# HP32W_proto.net
KiCad netlist of a schematic drawn in EAGLE
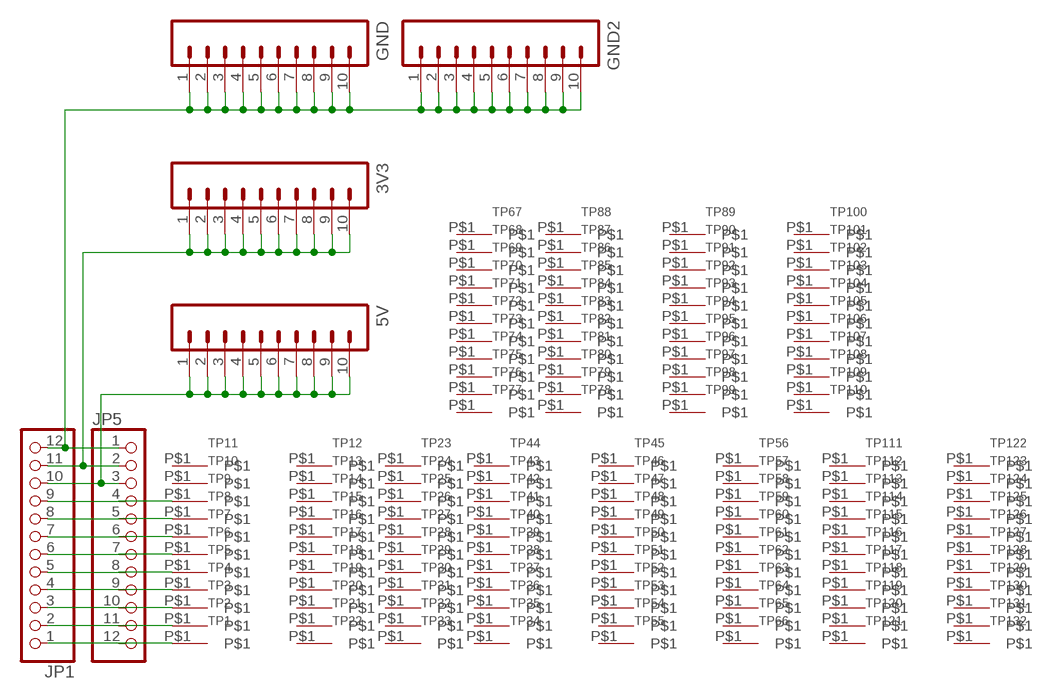
[diagram p0: schematic, sheet 1]

(export (version "E")
  (design (tool "Eeschema 10.0.6"))
  (components
    (comp (ref "3V3")
      (value "M10\"")
      (footprint "eagle-import:1X10")
      (libsource (lib "eagle-import") (part "M10{dblquote}"))
    )
    (comp (ref "5V")
      (value "M10\"")
      (footprint "eagle-import:1X10")
      (libsource (lib "eagle-import") (part "M10{dblquote}"))
    )
    (comp (ref "GND")
      (value "M10\"")
      (footprint "eagle-import:1X10")
      (libsource (lib "eagle-import") (part "M10{dblquote}"))
    )
    (comp (ref "GND2")
      (value "M10\"")
      (footprint "eagle-import:1X10")
      (libsource (lib "eagle-import") (part "M10{dblquote}"))
    )
    (comp (ref "JP1")
      (value "PINHD-1X12-CB")
      (footprint "eagle-import:1X12-CB")
      (libsource (lib "eagle-import") (part "PINHD-1X12-CB"))
    )
    (comp (ref "JP5")
      (value "PINHD-1X12-CB")
      (footprint "eagle-import:1X12-CB")
      (libsource (lib "eagle-import") (part "PINHD-1X12-CB"))
    )
    (comp (ref "TP1")
      (value "FLOWERPIN")
      (footprint "eagle-import:FLOWERPIN")
      (libsource (lib "eagle-import") (part "FLOWERPIN"))
    )
    (comp (ref "TP2")
      (value "FLOWERPIN")
      (footprint "eagle-import:FLOWERPIN")
      (libsource (lib "eagle-import") (part "FLOWERPIN"))
    )
    (comp (ref "TP3")
      (value "FLOWERPIN")
      (footprint "eagle-import:FLOWERPIN")
      (libsource (lib "eagle-import") (part "FLOWERPIN"))
    )
    (comp (ref "TP4")
      (value "FLOWERPIN")
      (footprint "eagle-import:FLOWERPIN")
      (libsource (lib "eagle-import") (part "FLOWERPIN"))
    )
    (comp (ref "TP5")
      (value "FLOWERPIN")
      (footprint "eagle-import:FLOWERPIN")
      (libsource (lib "eagle-import") (part "FLOWERPIN"))
    )
    (comp (ref "TP6")
      (value "FLOWERPIN")
      (footprint "eagle-import:FLOWERPIN")
      (libsource (lib "eagle-import") (part "FLOWERPIN"))
    )
    (comp (ref "TP7")
      (value "FLOWERPIN")
      (footprint "eagle-import:FLOWERPIN")
      (libsource (lib "eagle-import") (part "FLOWERPIN"))
    )
    (comp (ref "TP8")
      (value "FLOWERPIN")
      (footprint "eagle-import:FLOWERPIN")
      (libsource (lib "eagle-import") (part "FLOWERPIN"))
    )
    (comp (ref "TP9")
      (value "FLOWERPIN")
      (footprint "eagle-import:FLOWERPIN")
      (libsource (lib "eagle-import") (part "FLOWERPIN"))
    )
    (comp (ref "TP10")
      (value "FLOWERPIN")
      (footprint "eagle-import:FLOWERPIN")
      (libsource (lib "eagle-import") (part "FLOWERPIN"))
    )
    (comp (ref "TP11")
      (value "FLOWERPIN")
      (footprint "eagle-import:FLOWERPIN")
      (libsource (lib "eagle-import") (part "FLOWERPIN"))
    )
    (comp (ref "TP12")
      (value "FLOWERPIN")
      (footprint "eagle-import:FLOWERPIN")
      (libsource (lib "eagle-import") (part "FLOWERPIN"))
    )
    (comp (ref "TP13")
      (value "FLOWERPIN")
      (footprint "eagle-import:FLOWERPIN")
      (libsource (lib "eagle-import") (part "FLOWERPIN"))
    )
    (comp (ref "TP14")
      (value "FLOWERPIN")
      (footprint "eagle-import:FLOWERPIN")
      (libsource (lib "eagle-import") (part "FLOWERPIN"))
    )
    (comp (ref "TP15")
      (value "FLOWERPIN")
      (footprint "eagle-import:FLOWERPIN")
      (libsource (lib "eagle-import") (part "FLOWERPIN"))
    )
    (comp (ref "TP16")
      (value "FLOWERPIN")
      (footprint "eagle-import:FLOWERPIN")
      (libsource (lib "eagle-import") (part "FLOWERPIN"))
    )
    (comp (ref "TP17")
      (value "FLOWERPIN")
      (footprint "eagle-import:FLOWERPIN")
      (libsource (lib "eagle-import") (part "FLOWERPIN"))
    )
    (comp (ref "TP18")
      (value "FLOWERPIN")
      (footprint "eagle-import:FLOWERPIN")
      (libsource (lib "eagle-import") (part "FLOWERPIN"))
    )
    (comp (ref "TP19")
      (value "FLOWERPIN")
      (footprint "eagle-import:FLOWERPIN")
      (libsource (lib "eagle-import") (part "FLOWERPIN"))
    )
    (comp (ref "TP20")
      (value "FLOWERPIN")
      (footprint "eagle-import:FLOWERPIN")
      (libsource (lib "eagle-import") (part "FLOWERPIN"))
    )
    (comp (ref "TP21")
      (value "FLOWERPIN")
      (footprint "eagle-import:FLOWERPIN")
      (libsource (lib "eagle-import") (part "FLOWERPIN"))
    )
    (comp (ref "TP22")
      (value "FLOWERPIN")
      (footprint "eagle-import:FLOWERPIN")
      (libsource (lib "eagle-import") (part "FLOWERPIN"))
    )
    (comp (ref "TP23")
      (value "FLOWERPIN")
      (footprint "eagle-import:FLOWERPIN")
      (libsource (lib "eagle-import") (part "FLOWERPIN"))
    )
    (comp (ref "TP24")
      (value "FLOWERPIN")
      (footprint "eagle-import:FLOWERPIN")
      (libsource (lib "eagle-import") (part "FLOWERPIN"))
    )
    (comp (ref "TP25")
      (value "FLOWERPIN")
      (footprint "eagle-import:FLOWERPIN")
      (libsource (lib "eagle-import") (part "FLOWERPIN"))
    )
    (comp (ref "TP26")
      (value "FLOWERPIN")
      (footprint "eagle-import:FLOWERPIN")
      (libsource (lib "eagle-import") (part "FLOWERPIN"))
    )
    (comp (ref "TP27")
      (value "FLOWERPIN")
      (footprint "eagle-import:FLOWERPIN")
      (libsource (lib "eagle-import") (part "FLOWERPIN"))
    )
    (comp (ref "TP28")
      (value "FLOWERPIN")
      (footprint "eagle-import:FLOWERPIN")
      (libsource (lib "eagle-import") (part "FLOWERPIN"))
    )
    (comp (ref "TP29")
      (value "FLOWERPIN")
      (footprint "eagle-import:FLOWERPIN")
      (libsource (lib "eagle-import") (part "FLOWERPIN"))
    )
    (comp (ref "TP30")
      (value "FLOWERPIN")
      (footprint "eagle-import:FLOWERPIN")
      (libsource (lib "eagle-import") (part "FLOWERPIN"))
    )
    (comp (ref "TP31")
      (value "FLOWERPIN")
      (footprint "eagle-import:FLOWERPIN")
      (libsource (lib "eagle-import") (part "FLOWERPIN"))
    )
    (comp (ref "TP32")
      (value "FLOWERPIN")
      (footprint "eagle-import:FLOWERPIN")
      (libsource (lib "eagle-import") (part "FLOWERPIN"))
    )
    (comp (ref "TP33")
      (value "FLOWERPIN")
      (footprint "eagle-import:FLOWERPIN")
      (libsource (lib "eagle-import") (part "FLOWERPIN"))
    )
    (comp (ref "TP34")
      (value "FLOWERPIN")
      (footprint "eagle-import:FLOWERPIN")
      (libsource (lib "eagle-import") (part "FLOWERPIN"))
    )
    (comp (ref "TP35")
      (value "FLOWERPIN")
      (footprint "eagle-import:FLOWERPIN")
      (libsource (lib "eagle-import") (part "FLOWERPIN"))
    )
    (comp (ref "TP36")
      (value "FLOWERPIN")
      (footprint "eagle-import:FLOWERPIN")
      (libsource (lib "eagle-import") (part "FLOWERPIN"))
    )
    (comp (ref "TP37")
      (value "FLOWERPIN")
      (footprint "eagle-import:FLOWERPIN")
      (libsource (lib "eagle-import") (part "FLOWERPIN"))
    )
    (comp (ref "TP38")
      (value "FLOWERPIN")
      (footprint "eagle-import:FLOWERPIN")
      (libsource (lib "eagle-import") (part "FLOWERPIN"))
    )
    (comp (ref "TP39")
      (value "FLOWERPIN")
      (footprint "eagle-import:FLOWERPIN")
      (libsource (lib "eagle-import") (part "FLOWERPIN"))
    )
    (comp (ref "TP40")
      (value "FLOWERPIN")
      (footprint "eagle-import:FLOWERPIN")
      (libsource (lib "eagle-import") (part "FLOWERPIN"))
    )
    (comp (ref "TP41")
      (value "FLOWERPIN")
      (footprint "eagle-import:FLOWERPIN")
      (libsource (lib "eagle-import") (part "FLOWERPIN"))
    )
    (comp (ref "TP42")
      (value "FLOWERPIN")
      (footprint "eagle-import:FLOWERPIN")
      (libsource (lib "eagle-import") (part "FLOWERPIN"))
    )
    (comp (ref "TP43")
      (value "FLOWERPIN")
      (footprint "eagle-import:FLOWERPIN")
      (libsource (lib "eagle-import") (part "FLOWERPIN"))
    )
    (comp (ref "TP44")
      (value "FLOWERPIN")
      (footprint "eagle-import:FLOWERPIN")
      (libsource (lib "eagle-import") (part "FLOWERPIN"))
    )
    (comp (ref "TP45")
      (value "FLOWERPIN")
      (footprint "eagle-import:FLOWERPIN")
      (libsource (lib "eagle-import") (part "FLOWERPIN"))
    )
    (comp (ref "TP46")
      (value "FLOWERPIN")
      (footprint "eagle-import:FLOWERPIN")
      (libsource (lib "eagle-import") (part "FLOWERPIN"))
    )
    (comp (ref "TP47")
      (value "FLOWERPIN")
      (footprint "eagle-import:FLOWERPIN")
      (libsource (lib "eagle-import") (part "FLOWERPIN"))
    )
    (comp (ref "TP48")
      (value "FLOWERPIN")
      (footprint "eagle-import:FLOWERPIN")
      (libsource (lib "eagle-import") (part "FLOWERPIN"))
    )
    (comp (ref "TP49")
      (value "FLOWERPIN")
      (footprint "eagle-import:FLOWERPIN")
      (libsource (lib "eagle-import") (part "FLOWERPIN"))
    )
    (comp (ref "TP50")
      (value "FLOWERPIN")
      (footprint "eagle-import:FLOWERPIN")
      (libsource (lib "eagle-import") (part "FLOWERPIN"))
    )
    (comp (ref "TP51")
      (value "FLOWERPIN")
      (footprint "eagle-import:FLOWERPIN")
      (libsource (lib "eagle-import") (part "FLOWERPIN"))
    )
    (comp (ref "TP52")
      (value "FLOWERPIN")
      (footprint "eagle-import:FLOWERPIN")
      (libsource (lib "eagle-import") (part "FLOWERPIN"))
    )
    (comp (ref "TP53")
      (value "FLOWERPIN")
      (footprint "eagle-import:FLOWERPIN")
      (libsource (lib "eagle-import") (part "FLOWERPIN"))
    )
    (comp (ref "TP54")
      (value "FLOWERPIN")
      (footprint "eagle-import:FLOWERPIN")
      (libsource (lib "eagle-import") (part "FLOWERPIN"))
    )
    (comp (ref "TP55")
      (value "FLOWERPIN")
      (footprint "eagle-import:FLOWERPIN")
      (libsource (lib "eagle-import") (part "FLOWERPIN"))
    )
    (comp (ref "TP56")
      (value "FLOWERPIN")
      (footprint "eagle-import:FLOWERPIN")
      (libsource (lib "eagle-import") (part "FLOWERPIN"))
    )
    (comp (ref "TP57")
      (value "FLOWERPIN")
      (footprint "eagle-import:FLOWERPIN")
      (libsource (lib "eagle-import") (part "FLOWERPIN"))
    )
    (comp (ref "TP58")
      (value "FLOWERPIN")
      (footprint "eagle-import:FLOWERPIN")
      (libsource (lib "eagle-import") (part "FLOWERPIN"))
    )
    (comp (ref "TP59")
      (value "FLOWERPIN")
      (footprint "eagle-import:FLOWERPIN")
      (libsource (lib "eagle-import") (part "FLOWERPIN"))
    )
    (comp (ref "TP60")
      (value "FLOWERPIN")
      (footprint "eagle-import:FLOWERPIN")
      (libsource (lib "eagle-import") (part "FLOWERPIN"))
    )
    (comp (ref "TP61")
      (value "FLOWERPIN")
      (footprint "eagle-import:FLOWERPIN")
      (libsource (lib "eagle-import") (part "FLOWERPIN"))
    )
    (comp (ref "TP62")
      (value "FLOWERPIN")
      (footprint "eagle-import:FLOWERPIN")
      (libsource (lib "eagle-import") (part "FLOWERPIN"))
    )
    (comp (ref "TP63")
      (value "FLOWERPIN")
      (footprint "eagle-import:FLOWERPIN")
      (libsource (lib "eagle-import") (part "FLOWERPIN"))
    )
    (comp (ref "TP64")
      (value "FLOWERPIN")
      (footprint "eagle-import:FLOWERPIN")
      (libsource (lib "eagle-import") (part "FLOWERPIN"))
    )
    (comp (ref "TP65")
      (value "FLOWERPIN")
      (footprint "eagle-import:FLOWERPIN")
      (libsource (lib "eagle-import") (part "FLOWERPIN"))
    )
    (comp (ref "TP66")
      (value "FLOWERPIN")
      (footprint "eagle-import:FLOWERPIN")
      (libsource (lib "eagle-import") (part "FLOWERPIN"))
    )
    (comp (ref "TP67")
      (value "FLOWERPIN")
      (footprint "eagle-import:FLOWERPIN")
      (libsource (lib "eagle-import") (part "FLOWERPIN"))
    )
    (comp (ref "TP68")
      (value "FLOWERPIN")
      (footprint "eagle-import:FLOWERPIN")
      (libsource (lib "eagle-import") (part "FLOWERPIN"))
    )
    (comp (ref "TP69")
      (value "FLOWERPIN")
      (footprint "eagle-import:FLOWERPIN")
      (libsource (lib "eagle-import") (part "FLOWERPIN"))
    )
    (comp (ref "TP70")
      (value "FLOWERPIN")
      (footprint "eagle-import:FLOWERPIN")
      (libsource (lib "eagle-import") (part "FLOWERPIN"))
    )
    (comp (ref "TP71")
      (value "FLOWERPIN")
      (footprint "eagle-import:FLOWERPIN")
      (libsource (lib "eagle-import") (part "FLOWERPIN"))
    )
    (comp (ref "TP72")
      (value "FLOWERPIN")
      (footprint "eagle-import:FLOWERPIN")
      (libsource (lib "eagle-import") (part "FLOWERPIN"))
    )
    (comp (ref "TP73")
      (value "FLOWERPIN")
      (footprint "eagle-import:FLOWERPIN")
      (libsource (lib "eagle-import") (part "FLOWERPIN"))
    )
    (comp (ref "TP74")
      (value "FLOWERPIN")
      (footprint "eagle-import:FLOWERPIN")
      (libsource (lib "eagle-import") (part "FLOWERPIN"))
    )
    (comp (ref "TP75")
      (value "FLOWERPIN")
      (footprint "eagle-import:FLOWERPIN")
      (libsource (lib "eagle-import") (part "FLOWERPIN"))
    )
    (comp (ref "TP76")
      (value "FLOWERPIN")
      (footprint "eagle-import:FLOWERPIN")
      (libsource (lib "eagle-import") (part "FLOWERPIN"))
    )
    (comp (ref "TP77")
      (value "FLOWERPIN")
      (footprint "eagle-import:FLOWERPIN")
      (libsource (lib "eagle-import") (part "FLOWERPIN"))
    )
    (comp (ref "TP78")
      (value "FLOWERPIN")
      (footprint "eagle-import:FLOWERPIN")
      (libsource (lib "eagle-import") (part "FLOWERPIN"))
    )
    (comp (ref "TP79")
      (value "FLOWERPIN")
      (footprint "eagle-import:FLOWERPIN")
      (libsource (lib "eagle-import") (part "FLOWERPIN"))
    )
    (comp (ref "TP80")
      (value "FLOWERPIN")
      (footprint "eagle-import:FLOWERPIN")
      (libsource (lib "eagle-import") (part "FLOWERPIN"))
    )
    (comp (ref "TP81")
      (value "FLOWERPIN")
      (footprint "eagle-import:FLOWERPIN")
      (libsource (lib "eagle-import") (part "FLOWERPIN"))
    )
    (comp (ref "TP82")
      (value "FLOWERPIN")
      (footprint "eagle-import:FLOWERPIN")
      (libsource (lib "eagle-import") (part "FLOWERPIN"))
    )
    (comp (ref "TP83")
      (value "FLOWERPIN")
      (footprint "eagle-import:FLOWERPIN")
      (libsource (lib "eagle-import") (part "FLOWERPIN"))
    )
    (comp (ref "TP84")
      (value "FLOWERPIN")
      (footprint "eagle-import:FLOWERPIN")
      (libsource (lib "eagle-import") (part "FLOWERPIN"))
    )
    (comp (ref "TP85")
      (value "FLOWERPIN")
      (footprint "eagle-import:FLOWERPIN")
      (libsource (lib "eagle-import") (part "FLOWERPIN"))
    )
    (comp (ref "TP86")
      (value "FLOWERPIN")
      (footprint "eagle-import:FLOWERPIN")
      (libsource (lib "eagle-import") (part "FLOWERPIN"))
    )
    (comp (ref "TP87")
      (value "FLOWERPIN")
      (footprint "eagle-import:FLOWERPIN")
      (libsource (lib "eagle-import") (part "FLOWERPIN"))
    )
    (comp (ref "TP88")
      (value "FLOWERPIN")
      (footprint "eagle-import:FLOWERPIN")
      (libsource (lib "eagle-import") (part "FLOWERPIN"))
    )
    (comp (ref "TP89")
      (value "FLOWERPIN")
      (footprint "eagle-import:FLOWERPIN")
      (libsource (lib "eagle-import") (part "FLOWERPIN"))
    )
    (comp (ref "TP90")
      (value "FLOWERPIN")
      (footprint "eagle-import:FLOWERPIN")
      (libsource (lib "eagle-import") (part "FLOWERPIN"))
    )
    (comp (ref "TP91")
      (value "FLOWERPIN")
      (footprint "eagle-import:FLOWERPIN")
      (libsource (lib "eagle-import") (part "FLOWERPIN"))
    )
    (comp (ref "TP92")
      (value "FLOWERPIN")
      (footprint "eagle-import:FLOWERPIN")
      (libsource (lib "eagle-import") (part "FLOWERPIN"))
    )
    (comp (ref "TP93")
      (value "FLOWERPIN")
      (footprint "eagle-import:FLOWERPIN")
      (libsource (lib "eagle-import") (part "FLOWERPIN"))
    )
    (comp (ref "TP94")
      (value "FLOWERPIN")
      (footprint "eagle-import:FLOWERPIN")
      (libsource (lib "eagle-import") (part "FLOWERPIN"))
    )
    (comp (ref "TP95")
      (value "FLOWERPIN")
      (footprint "eagle-import:FLOWERPIN")
      (libsource (lib "eagle-import") (part "FLOWERPIN"))
    )
    (comp (ref "TP96")
      (value "FLOWERPIN")
      (footprint "eagle-import:FLOWERPIN")
      (libsource (lib "eagle-import") (part "FLOWERPIN"))
    )
    (comp (ref "TP97")
      (value "FLOWERPIN")
      (footprint "eagle-import:FLOWERPIN")
      (libsource (lib "eagle-import") (part "FLOWERPIN"))
    )
    (comp (ref "TP98")
      (value "FLOWERPIN")
      (footprint "eagle-import:FLOWERPIN")
      (libsource (lib "eagle-import") (part "FLOWERPIN"))
    )
    (comp (ref "TP99")
      (value "FLOWERPIN")
      (footprint "eagle-import:FLOWERPIN")
      (libsource (lib "eagle-import") (part "FLOWERPIN"))
    )
    (comp (ref "TP100")
      (value "FLOWERPIN")
      (footprint "eagle-import:FLOWERPIN")
      (libsource (lib "eagle-import") (part "FLOWERPIN"))
    )
    (comp (ref "TP101")
      (value "FLOWERPIN")
      (footprint "eagle-import:FLOWERPIN")
      (libsource (lib "eagle-import") (part "FLOWERPIN"))
    )
    (comp (ref "TP102")
      (value "FLOWERPIN")
      (footprint "eagle-import:FLOWERPIN")
      (libsource (lib "eagle-import") (part "FLOWERPIN"))
    )
    (comp (ref "TP103")
      (value "FLOWERPIN")
      (footprint "eagle-import:FLOWERPIN")
      (libsource (lib "eagle-import") (part "FLOWERPIN"))
    )
    (comp (ref "TP104")
      (value "FLOWERPIN")
      (footprint "eagle-import:FLOWERPIN")
      (libsource (lib "eagle-import") (part "FLOWERPIN"))
    )
    (comp (ref "TP105")
      (value "FLOWERPIN")
      (footprint "eagle-import:FLOWERPIN")
      (libsource (lib "eagle-import") (part "FLOWERPIN"))
    )
    (comp (ref "TP106")
      (value "FLOWERPIN")
      (footprint "eagle-import:FLOWERPIN")
      (libsource (lib "eagle-import") (part "FLOWERPIN"))
    )
    (comp (ref "TP107")
      (value "FLOWERPIN")
      (footprint "eagle-import:FLOWERPIN")
      (libsource (lib "eagle-import") (part "FLOWERPIN"))
    )
    (comp (ref "TP108")
      (value "FLOWERPIN")
      (footprint "eagle-import:FLOWERPIN")
      (libsource (lib "eagle-import") (part "FLOWERPIN"))
    )
    (comp (ref "TP109")
      (value "FLOWERPIN")
      (footprint "eagle-import:FLOWERPIN")
      (libsource (lib "eagle-import") (part "FLOWERPIN"))
    )
    (comp (ref "TP110")
      (value "FLOWERPIN")
      (footprint "eagle-import:FLOWERPIN")
      (libsource (lib "eagle-import") (part "FLOWERPIN"))
    )
    (comp (ref "TP111")
      (value "FLOWERPIN")
      (footprint "eagle-import:FLOWERPIN")
      (libsource (lib "eagle-import") (part "FLOWERPIN"))
    )
    (comp (ref "TP112")
      (value "FLOWERPIN")
      (footprint "eagle-import:FLOWERPIN")
      (libsource (lib "eagle-import") (part "FLOWERPIN"))
    )
    (comp (ref "TP113")
      (value "FLOWERPIN")
      (footprint "eagle-import:FLOWERPIN")
      (libsource (lib "eagle-import") (part "FLOWERPIN"))
    )
    (comp (ref "TP114")
      (value "FLOWERPIN")
      (footprint "eagle-import:FLOWERPIN")
      (libsource (lib "eagle-import") (part "FLOWERPIN"))
    )
    (comp (ref "TP115")
      (value "FLOWERPIN")
      (footprint "eagle-import:FLOWERPIN")
      (libsource (lib "eagle-import") (part "FLOWERPIN"))
    )
    (comp (ref "TP116")
      (value "FLOWERPIN")
      (footprint "eagle-import:FLOWERPIN")
      (libsource (lib "eagle-import") (part "FLOWERPIN"))
    )
    (comp (ref "TP117")
      (value "FLOWERPIN")
      (footprint "eagle-import:FLOWERPIN")
      (libsource (lib "eagle-import") (part "FLOWERPIN"))
    )
    (comp (ref "TP118")
      (value "FLOWERPIN")
      (footprint "eagle-import:FLOWERPIN")
      (libsource (lib "eagle-import") (part "FLOWERPIN"))
    )
    (comp (ref "TP119")
      (value "FLOWERPIN")
      (footprint "eagle-import:FLOWERPIN")
      (libsource (lib "eagle-import") (part "FLOWERPIN"))
    )
    (comp (ref "TP120")
      (value "FLOWERPIN")
      (footprint "eagle-import:FLOWERPIN")
      (libsource (lib "eagle-import") (part "FLOWERPIN"))
    )
    (comp (ref "TP121")
      (value "FLOWERPIN")
      (footprint "eagle-import:FLOWERPIN")
      (libsource (lib "eagle-import") (part "FLOWERPIN"))
    )
    (comp (ref "TP122")
      (value "FLOWERPIN")
      (footprint "eagle-import:FLOWERPIN")
      (libsource (lib "eagle-import") (part "FLOWERPIN"))
    )
    (comp (ref "TP123")
      (value "FLOWERPIN")
      (footprint "eagle-import:FLOWERPIN")
      (libsource (lib "eagle-import") (part "FLOWERPIN"))
    )
    (comp (ref "TP124")
      (value "FLOWERPIN")
      (footprint "eagle-import:FLOWERPIN")
      (libsource (lib "eagle-import") (part "FLOWERPIN"))
    )
    (comp (ref "TP125")
      (value "FLOWERPIN")
      (footprint "eagle-import:FLOWERPIN")
      (libsource (lib "eagle-import") (part "FLOWERPIN"))
    )
    (comp (ref "TP126")
      (value "FLOWERPIN")
      (footprint "eagle-import:FLOWERPIN")
      (libsource (lib "eagle-import") (part "FLOWERPIN"))
    )
    (comp (ref "TP127")
      (value "FLOWERPIN")
      (footprint "eagle-import:FLOWERPIN")
      (libsource (lib "eagle-import") (part "FLOWERPIN"))
    )
    (comp (ref "TP128")
      (value "FLOWERPIN")
      (footprint "eagle-import:FLOWERPIN")
      (libsource (lib "eagle-import") (part "FLOWERPIN"))
    )
    (comp (ref "TP129")
      (value "FLOWERPIN")
      (footprint "eagle-import:FLOWERPIN")
      (libsource (lib "eagle-import") (part "FLOWERPIN"))
    )
    (comp (ref "TP130")
      (value "FLOWERPIN")
      (footprint "eagle-import:FLOWERPIN")
      (libsource (lib "eagle-import") (part "FLOWERPIN"))
    )
    (comp (ref "TP131")
      (value "FLOWERPIN")
      (footprint "eagle-import:FLOWERPIN")
      (libsource (lib "eagle-import") (part "FLOWERPIN"))
    )
    (comp (ref "TP132")
      (value "FLOWERPIN")
      (footprint "eagle-import:FLOWERPIN")
      (libsource (lib "eagle-import") (part "FLOWERPIN"))
    )
  )
  (nets
    (net (code "1") (name "Net-(3V3-Pad1)") (class "Default")
      (node (ref "3V3") (pin "1") (pinfunction "1_1") (pintype "passive"))
      (node (ref "3V3") (pin "10") (pinfunction "10_10") (pintype "passive"))
      (node (ref "3V3") (pin "2") (pinfunction "2_2") (pintype "passive"))
      (node (ref "3V3") (pin "3") (pinfunction "3_3") (pintype "passive"))
      (node (ref "3V3") (pin "4") (pinfunction "4_4") (pintype "passive"))
      (node (ref "3V3") (pin "5") (pinfunction "5_5") (pintype "passive"))
      (node (ref "3V3") (pin "6") (pinfunction "6_6") (pintype "passive"))
      (node (ref "3V3") (pin "7") (pinfunction "7_7") (pintype "passive"))
      (node (ref "3V3") (pin "8") (pinfunction "8_8") (pintype "passive"))
      (node (ref "3V3") (pin "9") (pinfunction "9_9") (pintype "passive"))
      (node (ref "JP1") (pin "11") (pinfunction "11_11") (pintype "passive"))
      (node (ref "JP5") (pin "2") (pinfunction "2_2") (pintype "passive"))
    )
    (net (code "2") (name "Net-(5V-Pad1)") (class "Default")
      (node (ref "5V") (pin "1") (pinfunction "1_1") (pintype "passive"))
      (node (ref "5V") (pin "10") (pinfunction "10_10") (pintype "passive"))
      (node (ref "5V") (pin "2") (pinfunction "2_2") (pintype "passive"))
      (node (ref "5V") (pin "3") (pinfunction "3_3") (pintype "passive"))
      (node (ref "5V") (pin "4") (pinfunction "4_4") (pintype "passive"))
      (node (ref "5V") (pin "5") (pinfunction "5_5") (pintype "passive"))
      (node (ref "5V") (pin "6") (pinfunction "6_6") (pintype "passive"))
      (node (ref "5V") (pin "7") (pinfunction "7_7") (pintype "passive"))
      (node (ref "5V") (pin "8") (pinfunction "8_8") (pintype "passive"))
      (node (ref "5V") (pin "9") (pinfunction "9_9") (pintype "passive"))
      (node (ref "JP1") (pin "10") (pinfunction "10_10") (pintype "passive"))
      (node (ref "JP5") (pin "3") (pinfunction "3_3") (pintype "passive"))
    )
    (net (code "3") (name "Net-(GND-Pad1)") (class "Default")
      (node (ref "GND") (pin "1") (pinfunction "1_1") (pintype "passive"))
      (node (ref "GND") (pin "10") (pinfunction "10_10") (pintype "passive"))
      (node (ref "GND") (pin "2") (pinfunction "2_2") (pintype "passive"))
      (node (ref "GND") (pin "3") (pinfunction "3_3") (pintype "passive"))
      (node (ref "GND") (pin "4") (pinfunction "4_4") (pintype "passive"))
      (node (ref "GND") (pin "5") (pinfunction "5_5") (pintype "passive"))
      (node (ref "GND") (pin "6") (pinfunction "6_6") (pintype "passive"))
      (node (ref "GND") (pin "7") (pinfunction "7_7") (pintype "passive"))
      (node (ref "GND") (pin "8") (pinfunction "8_8") (pintype "passive"))
      (node (ref "GND") (pin "9") (pinfunction "9_9") (pintype "passive"))
      (node (ref "GND2") (pin "1") (pinfunction "1_1") (pintype "passive"))
      (node (ref "GND2") (pin "10") (pinfunction "10_10") (pintype "passive"))
      (node (ref "GND2") (pin "2") (pinfunction "2_2") (pintype "passive"))
      (node (ref "GND2") (pin "3") (pinfunction "3_3") (pintype "passive"))
      (node (ref "GND2") (pin "4") (pinfunction "4_4") (pintype "passive"))
      (node (ref "GND2") (pin "5") (pinfunction "5_5") (pintype "passive"))
      (node (ref "GND2") (pin "6") (pinfunction "6_6") (pintype "passive"))
      (node (ref "GND2") (pin "7") (pinfunction "7_7") (pintype "passive"))
      (node (ref "GND2") (pin "8") (pinfunction "8_8") (pintype "passive"))
      (node (ref "GND2") (pin "9") (pinfunction "9_9") (pintype "passive"))
      (node (ref "JP1") (pin "12") (pinfunction "12_12") (pintype "passive"))
      (node (ref "JP5") (pin "1") (pinfunction "1_1") (pintype "passive"))
    )
    (net (code "4") (name "Net-(JP1-Pad1)") (class "Default")
      (node (ref "JP1") (pin "1") (pinfunction "1_1") (pintype "passive"))
      (node (ref "JP5") (pin "12") (pinfunction "12_12") (pintype "passive"))
      (node (ref "TP1") (pin "P$1") (pinfunction "P$1_P$1") (pintype "bidirectional"))
    )
    (net (code "5") (name "Net-(JP1-Pad2)") (class "Default")
      (node (ref "JP1") (pin "2") (pinfunction "2_2") (pintype "passive"))
      (node (ref "JP5") (pin "11") (pinfunction "11_11") (pintype "passive"))
      (node (ref "TP2") (pin "P$1") (pinfunction "P$1_P$1") (pintype "bidirectional"))
    )
    (net (code "6") (name "Net-(JP1-Pad3)") (class "Default")
      (node (ref "JP1") (pin "3") (pinfunction "3_3") (pintype "passive"))
      (node (ref "JP5") (pin "10") (pinfunction "10_10") (pintype "passive"))
      (node (ref "TP3") (pin "P$1") (pinfunction "P$1_P$1") (pintype "bidirectional"))
    )
    (net (code "7") (name "Net-(JP1-Pad4)") (class "Default")
      (node (ref "JP1") (pin "4") (pinfunction "4_4") (pintype "passive"))
      (node (ref "JP5") (pin "9") (pinfunction "9_9") (pintype "passive"))
      (node (ref "TP4") (pin "P$1") (pinfunction "P$1_P$1") (pintype "bidirectional"))
    )
    (net (code "8") (name "Net-(JP1-Pad5)") (class "Default")
      (node (ref "JP1") (pin "5") (pinfunction "5_5") (pintype "passive"))
      (node (ref "JP5") (pin "8") (pinfunction "8_8") (pintype "passive"))
      (node (ref "TP5") (pin "P$1") (pinfunction "P$1_P$1") (pintype "bidirectional"))
    )
    (net (code "9") (name "Net-(JP1-Pad6)") (class "Default")
      (node (ref "JP1") (pin "6") (pinfunction "6_6") (pintype "passive"))
      (node (ref "JP5") (pin "7") (pinfunction "7_7") (pintype "passive"))
      (node (ref "TP6") (pin "P$1") (pinfunction "P$1_P$1") (pintype "bidirectional"))
    )
    (net (code "10") (name "Net-(JP1-Pad7)") (class "Default")
      (node (ref "JP1") (pin "7") (pinfunction "7_7") (pintype "passive"))
      (node (ref "JP5") (pin "6") (pinfunction "6_6") (pintype "passive"))
      (node (ref "TP7") (pin "P$1") (pinfunction "P$1_P$1") (pintype "bidirectional"))
    )
    (net (code "11") (name "Net-(JP1-Pad8)") (class "Default")
      (node (ref "JP1") (pin "8") (pinfunction "8_8") (pintype "passive"))
      (node (ref "JP5") (pin "5") (pinfunction "5_5") (pintype "passive"))
      (node (ref "TP8") (pin "P$1") (pinfunction "P$1_P$1") (pintype "bidirectional"))
    )
    (net (code "12") (name "Net-(JP1-Pad9)") (class "Default")
      (node (ref "JP1") (pin "9") (pinfunction "9_9") (pintype "passive"))
      (node (ref "JP5") (pin "4") (pinfunction "4_4") (pintype "passive"))
      (node (ref "TP9") (pin "P$1") (pinfunction "P$1_P$1") (pintype "bidirectional"))
    )
    (net (code "13") (name "unconnected-(TP10-PadP$1)") (class "Default")
      (node (ref "TP10") (pin "P$1") (pinfunction "P$1_P$1") (pintype "bidirectional"))
    )
    (net (code "14") (name "unconnected-(TP11-PadP$1)") (class "Default")
      (node (ref "TP11") (pin "P$1") (pinfunction "P$1_P$1") (pintype "bidirectional"))
    )
    (net (code "15") (name "unconnected-(TP12-PadP$1)") (class "Default")
      (node (ref "TP12") (pin "P$1") (pinfunction "P$1_P$1") (pintype "bidirectional"))
    )
    (net (code "16") (name "unconnected-(TP13-PadP$1)") (class "Default")
      (node (ref "TP13") (pin "P$1") (pinfunction "P$1_P$1") (pintype "bidirectional"))
    )
    (net (code "17") (name "unconnected-(TP14-PadP$1)") (class "Default")
      (node (ref "TP14") (pin "P$1") (pinfunction "P$1_P$1") (pintype "bidirectional"))
    )
    (net (code "18") (name "unconnected-(TP15-PadP$1)") (class "Default")
      (node (ref "TP15") (pin "P$1") (pinfunction "P$1_P$1") (pintype "bidirectional"))
    )
    (net (code "19") (name "unconnected-(TP16-PadP$1)") (class "Default")
      (node (ref "TP16") (pin "P$1") (pinfunction "P$1_P$1") (pintype "bidirectional"))
    )
    (net (code "20") (name "unconnected-(TP17-PadP$1)") (class "Default")
      (node (ref "TP17") (pin "P$1") (pinfunction "P$1_P$1") (pintype "bidirectional"))
    )
    (net (code "21") (name "unconnected-(TP18-PadP$1)") (class "Default")
      (node (ref "TP18") (pin "P$1") (pinfunction "P$1_P$1") (pintype "bidirectional"))
    )
    (net (code "22") (name "unconnected-(TP19-PadP$1)") (class "Default")
      (node (ref "TP19") (pin "P$1") (pinfunction "P$1_P$1") (pintype "bidirectional"))
    )
    (net (code "23") (name "unconnected-(TP20-PadP$1)") (class "Default")
      (node (ref "TP20") (pin "P$1") (pinfunction "P$1_P$1") (pintype "bidirectional"))
    )
    (net (code "24") (name "unconnected-(TP21-PadP$1)") (class "Default")
      (node (ref "TP21") (pin "P$1") (pinfunction "P$1_P$1") (pintype "bidirectional"))
    )
    (net (code "25") (name "unconnected-(TP22-PadP$1)") (class "Default")
      (node (ref "TP22") (pin "P$1") (pinfunction "P$1_P$1") (pintype "bidirectional"))
    )
    (net (code "26") (name "unconnected-(TP23-PadP$1)") (class "Default")
      (node (ref "TP23") (pin "P$1") (pinfunction "P$1_P$1") (pintype "bidirectional"))
    )
    (net (code "27") (name "unconnected-(TP24-PadP$1)") (class "Default")
      (node (ref "TP24") (pin "P$1") (pinfunction "P$1_P$1") (pintype "bidirectional"))
    )
    (net (code "28") (name "unconnected-(TP25-PadP$1)") (class "Default")
      (node (ref "TP25") (pin "P$1") (pinfunction "P$1_P$1") (pintype "bidirectional"))
    )
    (net (code "29") (name "unconnected-(TP26-PadP$1)") (class "Default")
      (node (ref "TP26") (pin "P$1") (pinfunction "P$1_P$1") (pintype "bidirectional"))
    )
    (net (code "30") (name "unconnected-(TP27-PadP$1)") (class "Default")
      (node (ref "TP27") (pin "P$1") (pinfunction "P$1_P$1") (pintype "bidirectional"))
    )
    (net (code "31") (name "unconnected-(TP28-PadP$1)") (class "Default")
      (node (ref "TP28") (pin "P$1") (pinfunction "P$1_P$1") (pintype "bidirectional"))
    )
    (net (code "32") (name "unconnected-(TP29-PadP$1)") (class "Default")
      (node (ref "TP29") (pin "P$1") (pinfunction "P$1_P$1") (pintype "bidirectional"))
    )
    (net (code "33") (name "unconnected-(TP30-PadP$1)") (class "Default")
      (node (ref "TP30") (pin "P$1") (pinfunction "P$1_P$1") (pintype "bidirectional"))
    )
    (net (code "34") (name "unconnected-(TP31-PadP$1)") (class "Default")
      (node (ref "TP31") (pin "P$1") (pinfunction "P$1_P$1") (pintype "bidirectional"))
    )
    (net (code "35") (name "unconnected-(TP32-PadP$1)") (class "Default")
      (node (ref "TP32") (pin "P$1") (pinfunction "P$1_P$1") (pintype "bidirectional"))
    )
    (net (code "36") (name "unconnected-(TP33-PadP$1)") (class "Default")
      (node (ref "TP33") (pin "P$1") (pinfunction "P$1_P$1") (pintype "bidirectional"))
    )
    (net (code "37") (name "unconnected-(TP34-PadP$1)") (class "Default")
      (node (ref "TP34") (pin "P$1") (pinfunction "P$1_P$1") (pintype "bidirectional"))
    )
    (net (code "38") (name "unconnected-(TP35-PadP$1)") (class "Default")
      (node (ref "TP35") (pin "P$1") (pinfunction "P$1_P$1") (pintype "bidirectional"))
    )
    (net (code "39") (name "unconnected-(TP36-PadP$1)") (class "Default")
      (node (ref "TP36") (pin "P$1") (pinfunction "P$1_P$1") (pintype "bidirectional"))
    )
    (net (code "40") (name "unconnected-(TP37-PadP$1)") (class "Default")
      (node (ref "TP37") (pin "P$1") (pinfunction "P$1_P$1") (pintype "bidirectional"))
    )
    (net (code "41") (name "unconnected-(TP38-PadP$1)") (class "Default")
      (node (ref "TP38") (pin "P$1") (pinfunction "P$1_P$1") (pintype "bidirectional"))
    )
    (net (code "42") (name "unconnected-(TP39-PadP$1)") (class "Default")
      (node (ref "TP39") (pin "P$1") (pinfunction "P$1_P$1") (pintype "bidirectional"))
    )
    (net (code "43") (name "unconnected-(TP40-PadP$1)") (class "Default")
      (node (ref "TP40") (pin "P$1") (pinfunction "P$1_P$1") (pintype "bidirectional"))
    )
    (net (code "44") (name "unconnected-(TP41-PadP$1)") (class "Default")
      (node (ref "TP41") (pin "P$1") (pinfunction "P$1_P$1") (pintype "bidirectional"))
    )
    (net (code "45") (name "unconnected-(TP42-PadP$1)") (class "Default")
      (node (ref "TP42") (pin "P$1") (pinfunction "P$1_P$1") (pintype "bidirectional"))
    )
    (net (code "46") (name "unconnected-(TP43-PadP$1)") (class "Default")
      (node (ref "TP43") (pin "P$1") (pinfunction "P$1_P$1") (pintype "bidirectional"))
    )
    (net (code "47") (name "unconnected-(TP44-PadP$1)") (class "Default")
      (node (ref "TP44") (pin "P$1") (pinfunction "P$1_P$1") (pintype "bidirectional"))
    )
    (net (code "48") (name "unconnected-(TP45-PadP$1)") (class "Default")
      (node (ref "TP45") (pin "P$1") (pinfunction "P$1_P$1") (pintype "bidirectional"))
    )
    (net (code "49") (name "unconnected-(TP46-PadP$1)") (class "Default")
      (node (ref "TP46") (pin "P$1") (pinfunction "P$1_P$1") (pintype "bidirectional"))
    )
    (net (code "50") (name "unconnected-(TP47-PadP$1)") (class "Default")
      (node (ref "TP47") (pin "P$1") (pinfunction "P$1_P$1") (pintype "bidirectional"))
    )
    (net (code "51") (name "unconnected-(TP48-PadP$1)") (class "Default")
      (node (ref "TP48") (pin "P$1") (pinfunction "P$1_P$1") (pintype "bidirectional"))
    )
    (net (code "52") (name "unconnected-(TP49-PadP$1)") (class "Default")
      (node (ref "TP49") (pin "P$1") (pinfunction "P$1_P$1") (pintype "bidirectional"))
    )
    (net (code "53") (name "unconnected-(TP50-PadP$1)") (class "Default")
      (node (ref "TP50") (pin "P$1") (pinfunction "P$1_P$1") (pintype "bidirectional"))
    )
    (net (code "54") (name "unconnected-(TP51-PadP$1)") (class "Default")
      (node (ref "TP51") (pin "P$1") (pinfunction "P$1_P$1") (pintype "bidirectional"))
    )
    (net (code "55") (name "unconnected-(TP52-PadP$1)") (class "Default")
      (node (ref "TP52") (pin "P$1") (pinfunction "P$1_P$1") (pintype "bidirectional"))
    )
    (net (code "56") (name "unconnected-(TP53-PadP$1)") (class "Default")
      (node (ref "TP53") (pin "P$1") (pinfunction "P$1_P$1") (pintype "bidirectional"))
    )
    (net (code "57") (name "unconnected-(TP54-PadP$1)") (class "Default")
      (node (ref "TP54") (pin "P$1") (pinfunction "P$1_P$1") (pintype "bidirectional"))
    )
    (net (code "58") (name "unconnected-(TP55-PadP$1)") (class "Default")
      (node (ref "TP55") (pin "P$1") (pinfunction "P$1_P$1") (pintype "bidirectional"))
    )
    (net (code "59") (name "unconnected-(TP56-PadP$1)") (class "Default")
      (node (ref "TP56") (pin "P$1") (pinfunction "P$1_P$1") (pintype "bidirectional"))
    )
    (net (code "60") (name "unconnected-(TP57-PadP$1)") (class "Default")
      (node (ref "TP57") (pin "P$1") (pinfunction "P$1_P$1") (pintype "bidirectional"))
    )
    (net (code "61") (name "unconnected-(TP58-PadP$1)") (class "Default")
      (node (ref "TP58") (pin "P$1") (pinfunction "P$1_P$1") (pintype "bidirectional"))
    )
    (net (code "62") (name "unconnected-(TP59-PadP$1)") (class "Default")
      (node (ref "TP59") (pin "P$1") (pinfunction "P$1_P$1") (pintype "bidirectional"))
    )
    (net (code "63") (name "unconnected-(TP60-PadP$1)") (class "Default")
      (node (ref "TP60") (pin "P$1") (pinfunction "P$1_P$1") (pintype "bidirectional"))
    )
    (net (code "64") (name "unconnected-(TP61-PadP$1)") (class "Default")
      (node (ref "TP61") (pin "P$1") (pinfunction "P$1_P$1") (pintype "bidirectional"))
    )
    (net (code "65") (name "unconnected-(TP62-PadP$1)") (class "Default")
      (node (ref "TP62") (pin "P$1") (pinfunction "P$1_P$1") (pintype "bidirectional"))
    )
    (net (code "66") (name "unconnected-(TP63-PadP$1)") (class "Default")
      (node (ref "TP63") (pin "P$1") (pinfunction "P$1_P$1") (pintype "bidirectional"))
    )
    (net (code "67") (name "unconnected-(TP64-PadP$1)") (class "Default")
      (node (ref "TP64") (pin "P$1") (pinfunction "P$1_P$1") (pintype "bidirectional"))
    )
    (net (code "68") (name "unconnected-(TP65-PadP$1)") (class "Default")
      (node (ref "TP65") (pin "P$1") (pinfunction "P$1_P$1") (pintype "bidirectional"))
    )
    (net (code "69") (name "unconnected-(TP66-PadP$1)") (class "Default")
      (node (ref "TP66") (pin "P$1") (pinfunction "P$1_P$1") (pintype "bidirectional"))
    )
    (net (code "70") (name "unconnected-(TP67-PadP$1)") (class "Default")
      (node (ref "TP67") (pin "P$1") (pinfunction "P$1_P$1") (pintype "bidirectional"))
    )
    (net (code "71") (name "unconnected-(TP68-PadP$1)") (class "Default")
      (node (ref "TP68") (pin "P$1") (pinfunction "P$1_P$1") (pintype "bidirectional"))
    )
    (net (code "72") (name "unconnected-(TP69-PadP$1)") (class "Default")
      (node (ref "TP69") (pin "P$1") (pinfunction "P$1_P$1") (pintype "bidirectional"))
    )
    (net (code "73") (name "unconnected-(TP70-PadP$1)") (class "Default")
      (node (ref "TP70") (pin "P$1") (pinfunction "P$1_P$1") (pintype "bidirectional"))
    )
    (net (code "74") (name "unconnected-(TP71-PadP$1)") (class "Default")
      (node (ref "TP71") (pin "P$1") (pinfunction "P$1_P$1") (pintype "bidirectional"))
    )
    (net (code "75") (name "unconnected-(TP72-PadP$1)") (class "Default")
      (node (ref "TP72") (pin "P$1") (pinfunction "P$1_P$1") (pintype "bidirectional"))
    )
    (net (code "76") (name "unconnected-(TP73-PadP$1)") (class "Default")
      (node (ref "TP73") (pin "P$1") (pinfunction "P$1_P$1") (pintype "bidirectional"))
    )
    (net (code "77") (name "unconnected-(TP74-PadP$1)") (class "Default")
      (node (ref "TP74") (pin "P$1") (pinfunction "P$1_P$1") (pintype "bidirectional"))
    )
    (net (code "78") (name "unconnected-(TP75-PadP$1)") (class "Default")
      (node (ref "TP75") (pin "P$1") (pinfunction "P$1_P$1") (pintype "bidirectional"))
    )
    (net (code "79") (name "unconnected-(TP76-PadP$1)") (class "Default")
      (node (ref "TP76") (pin "P$1") (pinfunction "P$1_P$1") (pintype "bidirectional"))
    )
    (net (code "80") (name "unconnected-(TP77-PadP$1)") (class "Default")
      (node (ref "TP77") (pin "P$1") (pinfunction "P$1_P$1") (pintype "bidirectional"))
    )
    (net (code "81") (name "unconnected-(TP78-PadP$1)") (class "Default")
      (node (ref "TP78") (pin "P$1") (pinfunction "P$1_P$1") (pintype "bidirectional"))
    )
    (net (code "82") (name "unconnected-(TP79-PadP$1)") (class "Default")
      (node (ref "TP79") (pin "P$1") (pinfunction "P$1_P$1") (pintype "bidirectional"))
    )
    (net (code "83") (name "unconnected-(TP80-PadP$1)") (class "Default")
      (node (ref "TP80") (pin "P$1") (pinfunction "P$1_P$1") (pintype "bidirectional"))
    )
    (net (code "84") (name "unconnected-(TP81-PadP$1)") (class "Default")
      (node (ref "TP81") (pin "P$1") (pinfunction "P$1_P$1") (pintype "bidirectional"))
    )
    (net (code "85") (name "unconnected-(TP82-PadP$1)") (class "Default")
      (node (ref "TP82") (pin "P$1") (pinfunction "P$1_P$1") (pintype "bidirectional"))
    )
    (net (code "86") (name "unconnected-(TP83-PadP$1)") (class "Default")
      (node (ref "TP83") (pin "P$1") (pinfunction "P$1_P$1") (pintype "bidirectional"))
    )
    (net (code "87") (name "unconnected-(TP84-PadP$1)") (class "Default")
      (node (ref "TP84") (pin "P$1") (pinfunction "P$1_P$1") (pintype "bidirectional"))
    )
    (net (code "88") (name "unconnected-(TP85-PadP$1)") (class "Default")
      (node (ref "TP85") (pin "P$1") (pinfunction "P$1_P$1") (pintype "bidirectional"))
    )
    (net (code "89") (name "unconnected-(TP86-PadP$1)") (class "Default")
      (node (ref "TP86") (pin "P$1") (pinfunction "P$1_P$1") (pintype "bidirectional"))
    )
    (net (code "90") (name "unconnected-(TP87-PadP$1)") (class "Default")
      (node (ref "TP87") (pin "P$1") (pinfunction "P$1_P$1") (pintype "bidirectional"))
    )
    (net (code "91") (name "unconnected-(TP88-PadP$1)") (class "Default")
      (node (ref "TP88") (pin "P$1") (pinfunction "P$1_P$1") (pintype "bidirectional"))
    )
    (net (code "92") (name "unconnected-(TP89-PadP$1)") (class "Default")
      (node (ref "TP89") (pin "P$1") (pinfunction "P$1_P$1") (pintype "bidirectional"))
    )
    (net (code "93") (name "unconnected-(TP90-PadP$1)") (class "Default")
      (node (ref "TP90") (pin "P$1") (pinfunction "P$1_P$1") (pintype "bidirectional"))
    )
    (net (code "94") (name "unconnected-(TP91-PadP$1)") (class "Default")
      (node (ref "TP91") (pin "P$1") (pinfunction "P$1_P$1") (pintype "bidirectional"))
    )
    (net (code "95") (name "unconnected-(TP92-PadP$1)") (class "Default")
      (node (ref "TP92") (pin "P$1") (pinfunction "P$1_P$1") (pintype "bidirectional"))
    )
    (net (code "96") (name "unconnected-(TP93-PadP$1)") (class "Default")
      (node (ref "TP93") (pin "P$1") (pinfunction "P$1_P$1") (pintype "bidirectional"))
    )
    (net (code "97") (name "unconnected-(TP94-PadP$1)") (class "Default")
      (node (ref "TP94") (pin "P$1") (pinfunction "P$1_P$1") (pintype "bidirectional"))
    )
    (net (code "98") (name "unconnected-(TP95-PadP$1)") (class "Default")
      (node (ref "TP95") (pin "P$1") (pinfunction "P$1_P$1") (pintype "bidirectional"))
    )
    (net (code "99") (name "unconnected-(TP96-PadP$1)") (class "Default")
      (node (ref "TP96") (pin "P$1") (pinfunction "P$1_P$1") (pintype "bidirectional"))
    )
    (net (code "100") (name "unconnected-(TP97-PadP$1)") (class "Default")
      (node (ref "TP97") (pin "P$1") (pinfunction "P$1_P$1") (pintype "bidirectional"))
    )
    (net (code "101") (name "unconnected-(TP98-PadP$1)") (class "Default")
      (node (ref "TP98") (pin "P$1") (pinfunction "P$1_P$1") (pintype "bidirectional"))
    )
    (net (code "102") (name "unconnected-(TP99-PadP$1)") (class "Default")
      (node (ref "TP99") (pin "P$1") (pinfunction "P$1_P$1") (pintype "bidirectional"))
    )
    (net (code "103") (name "unconnected-(TP100-PadP$1)") (class "Default")
      (node (ref "TP100") (pin "P$1") (pinfunction "P$1_P$1") (pintype "bidirectional"))
    )
    (net (code "104") (name "unconnected-(TP101-PadP$1)") (class "Default")
      (node (ref "TP101") (pin "P$1") (pinfunction "P$1_P$1") (pintype "bidirectional"))
    )
    (net (code "105") (name "unconnected-(TP102-PadP$1)") (class "Default")
      (node (ref "TP102") (pin "P$1") (pinfunction "P$1_P$1") (pintype "bidirectional"))
    )
    (net (code "106") (name "unconnected-(TP103-PadP$1)") (class "Default")
      (node (ref "TP103") (pin "P$1") (pinfunction "P$1_P$1") (pintype "bidirectional"))
    )
    (net (code "107") (name "unconnected-(TP104-PadP$1)") (class "Default")
      (node (ref "TP104") (pin "P$1") (pinfunction "P$1_P$1") (pintype "bidirectional"))
    )
    (net (code "108") (name "unconnected-(TP105-PadP$1)") (class "Default")
      (node (ref "TP105") (pin "P$1") (pinfunction "P$1_P$1") (pintype "bidirectional"))
    )
    (net (code "109") (name "unconnected-(TP106-PadP$1)") (class "Default")
      (node (ref "TP106") (pin "P$1") (pinfunction "P$1_P$1") (pintype "bidirectional"))
    )
    (net (code "110") (name "unconnected-(TP107-PadP$1)") (class "Default")
      (node (ref "TP107") (pin "P$1") (pinfunction "P$1_P$1") (pintype "bidirectional"))
    )
    (net (code "111") (name "unconnected-(TP108-PadP$1)") (class "Default")
      (node (ref "TP108") (pin "P$1") (pinfunction "P$1_P$1") (pintype "bidirectional"))
    )
    (net (code "112") (name "unconnected-(TP109-PadP$1)") (class "Default")
      (node (ref "TP109") (pin "P$1") (pinfunction "P$1_P$1") (pintype "bidirectional"))
    )
    (net (code "113") (name "unconnected-(TP110-PadP$1)") (class "Default")
      (node (ref "TP110") (pin "P$1") (pinfunction "P$1_P$1") (pintype "bidirectional"))
    )
    (net (code "114") (name "unconnected-(TP111-PadP$1)") (class "Default")
      (node (ref "TP111") (pin "P$1") (pinfunction "P$1_P$1") (pintype "bidirectional"))
    )
    (net (code "115") (name "unconnected-(TP112-PadP$1)") (class "Default")
      (node (ref "TP112") (pin "P$1") (pinfunction "P$1_P$1") (pintype "bidirectional"))
    )
    (net (code "116") (name "unconnected-(TP113-PadP$1)") (class "Default")
      (node (ref "TP113") (pin "P$1") (pinfunction "P$1_P$1") (pintype "bidirectional"))
    )
    (net (code "117") (name "unconnected-(TP114-PadP$1)") (class "Default")
      (node (ref "TP114") (pin "P$1") (pinfunction "P$1_P$1") (pintype "bidirectional"))
    )
    (net (code "118") (name "unconnected-(TP115-PadP$1)") (class "Default")
      (node (ref "TP115") (pin "P$1") (pinfunction "P$1_P$1") (pintype "bidirectional"))
    )
    (net (code "119") (name "unconnected-(TP116-PadP$1)") (class "Default")
      (node (ref "TP116") (pin "P$1") (pinfunction "P$1_P$1") (pintype "bidirectional"))
    )
    (net (code "120") (name "unconnected-(TP117-PadP$1)") (class "Default")
      (node (ref "TP117") (pin "P$1") (pinfunction "P$1_P$1") (pintype "bidirectional"))
    )
    (net (code "121") (name "unconnected-(TP118-PadP$1)") (class "Default")
      (node (ref "TP118") (pin "P$1") (pinfunction "P$1_P$1") (pintype "bidirectional"))
    )
    (net (code "122") (name "unconnected-(TP119-PadP$1)") (class "Default")
      (node (ref "TP119") (pin "P$1") (pinfunction "P$1_P$1") (pintype "bidirectional"))
    )
    (net (code "123") (name "unconnected-(TP120-PadP$1)") (class "Default")
      (node (ref "TP120") (pin "P$1") (pinfunction "P$1_P$1") (pintype "bidirectional"))
    )
    (net (code "124") (name "unconnected-(TP121-PadP$1)") (class "Default")
      (node (ref "TP121") (pin "P$1") (pinfunction "P$1_P$1") (pintype "bidirectional"))
    )
    (net (code "125") (name "unconnected-(TP122-PadP$1)") (class "Default")
      (node (ref "TP122") (pin "P$1") (pinfunction "P$1_P$1") (pintype "bidirectional"))
    )
    (net (code "126") (name "unconnected-(TP123-PadP$1)") (class "Default")
      (node (ref "TP123") (pin "P$1") (pinfunction "P$1_P$1") (pintype "bidirectional"))
    )
    (net (code "127") (name "unconnected-(TP124-PadP$1)") (class "Default")
      (node (ref "TP124") (pin "P$1") (pinfunction "P$1_P$1") (pintype "bidirectional"))
    )
    (net (code "128") (name "unconnected-(TP125-PadP$1)") (class "Default")
      (node (ref "TP125") (pin "P$1") (pinfunction "P$1_P$1") (pintype "bidirectional"))
    )
    (net (code "129") (name "unconnected-(TP126-PadP$1)") (class "Default")
      (node (ref "TP126") (pin "P$1") (pinfunction "P$1_P$1") (pintype "bidirectional"))
    )
    (net (code "130") (name "unconnected-(TP127-PadP$1)") (class "Default")
      (node (ref "TP127") (pin "P$1") (pinfunction "P$1_P$1") (pintype "bidirectional"))
    )
    (net (code "131") (name "unconnected-(TP128-PadP$1)") (class "Default")
      (node (ref "TP128") (pin "P$1") (pinfunction "P$1_P$1") (pintype "bidirectional"))
    )
    (net (code "132") (name "unconnected-(TP129-PadP$1)") (class "Default")
      (node (ref "TP129") (pin "P$1") (pinfunction "P$1_P$1") (pintype "bidirectional"))
    )
    (net (code "133") (name "unconnected-(TP130-PadP$1)") (class "Default")
      (node (ref "TP130") (pin "P$1") (pinfunction "P$1_P$1") (pintype "bidirectional"))
    )
    (net (code "134") (name "unconnected-(TP131-PadP$1)") (class "Default")
      (node (ref "TP131") (pin "P$1") (pinfunction "P$1_P$1") (pintype "bidirectional"))
    )
    (net (code "135") (name "unconnected-(TP132-PadP$1)") (class "Default")
      (node (ref "TP132") (pin "P$1") (pinfunction "P$1_P$1") (pintype "bidirectional"))
    )
  )
)
